# RPi_relay_board.net
KiCad netlist of a schematic drawn in EAGLE
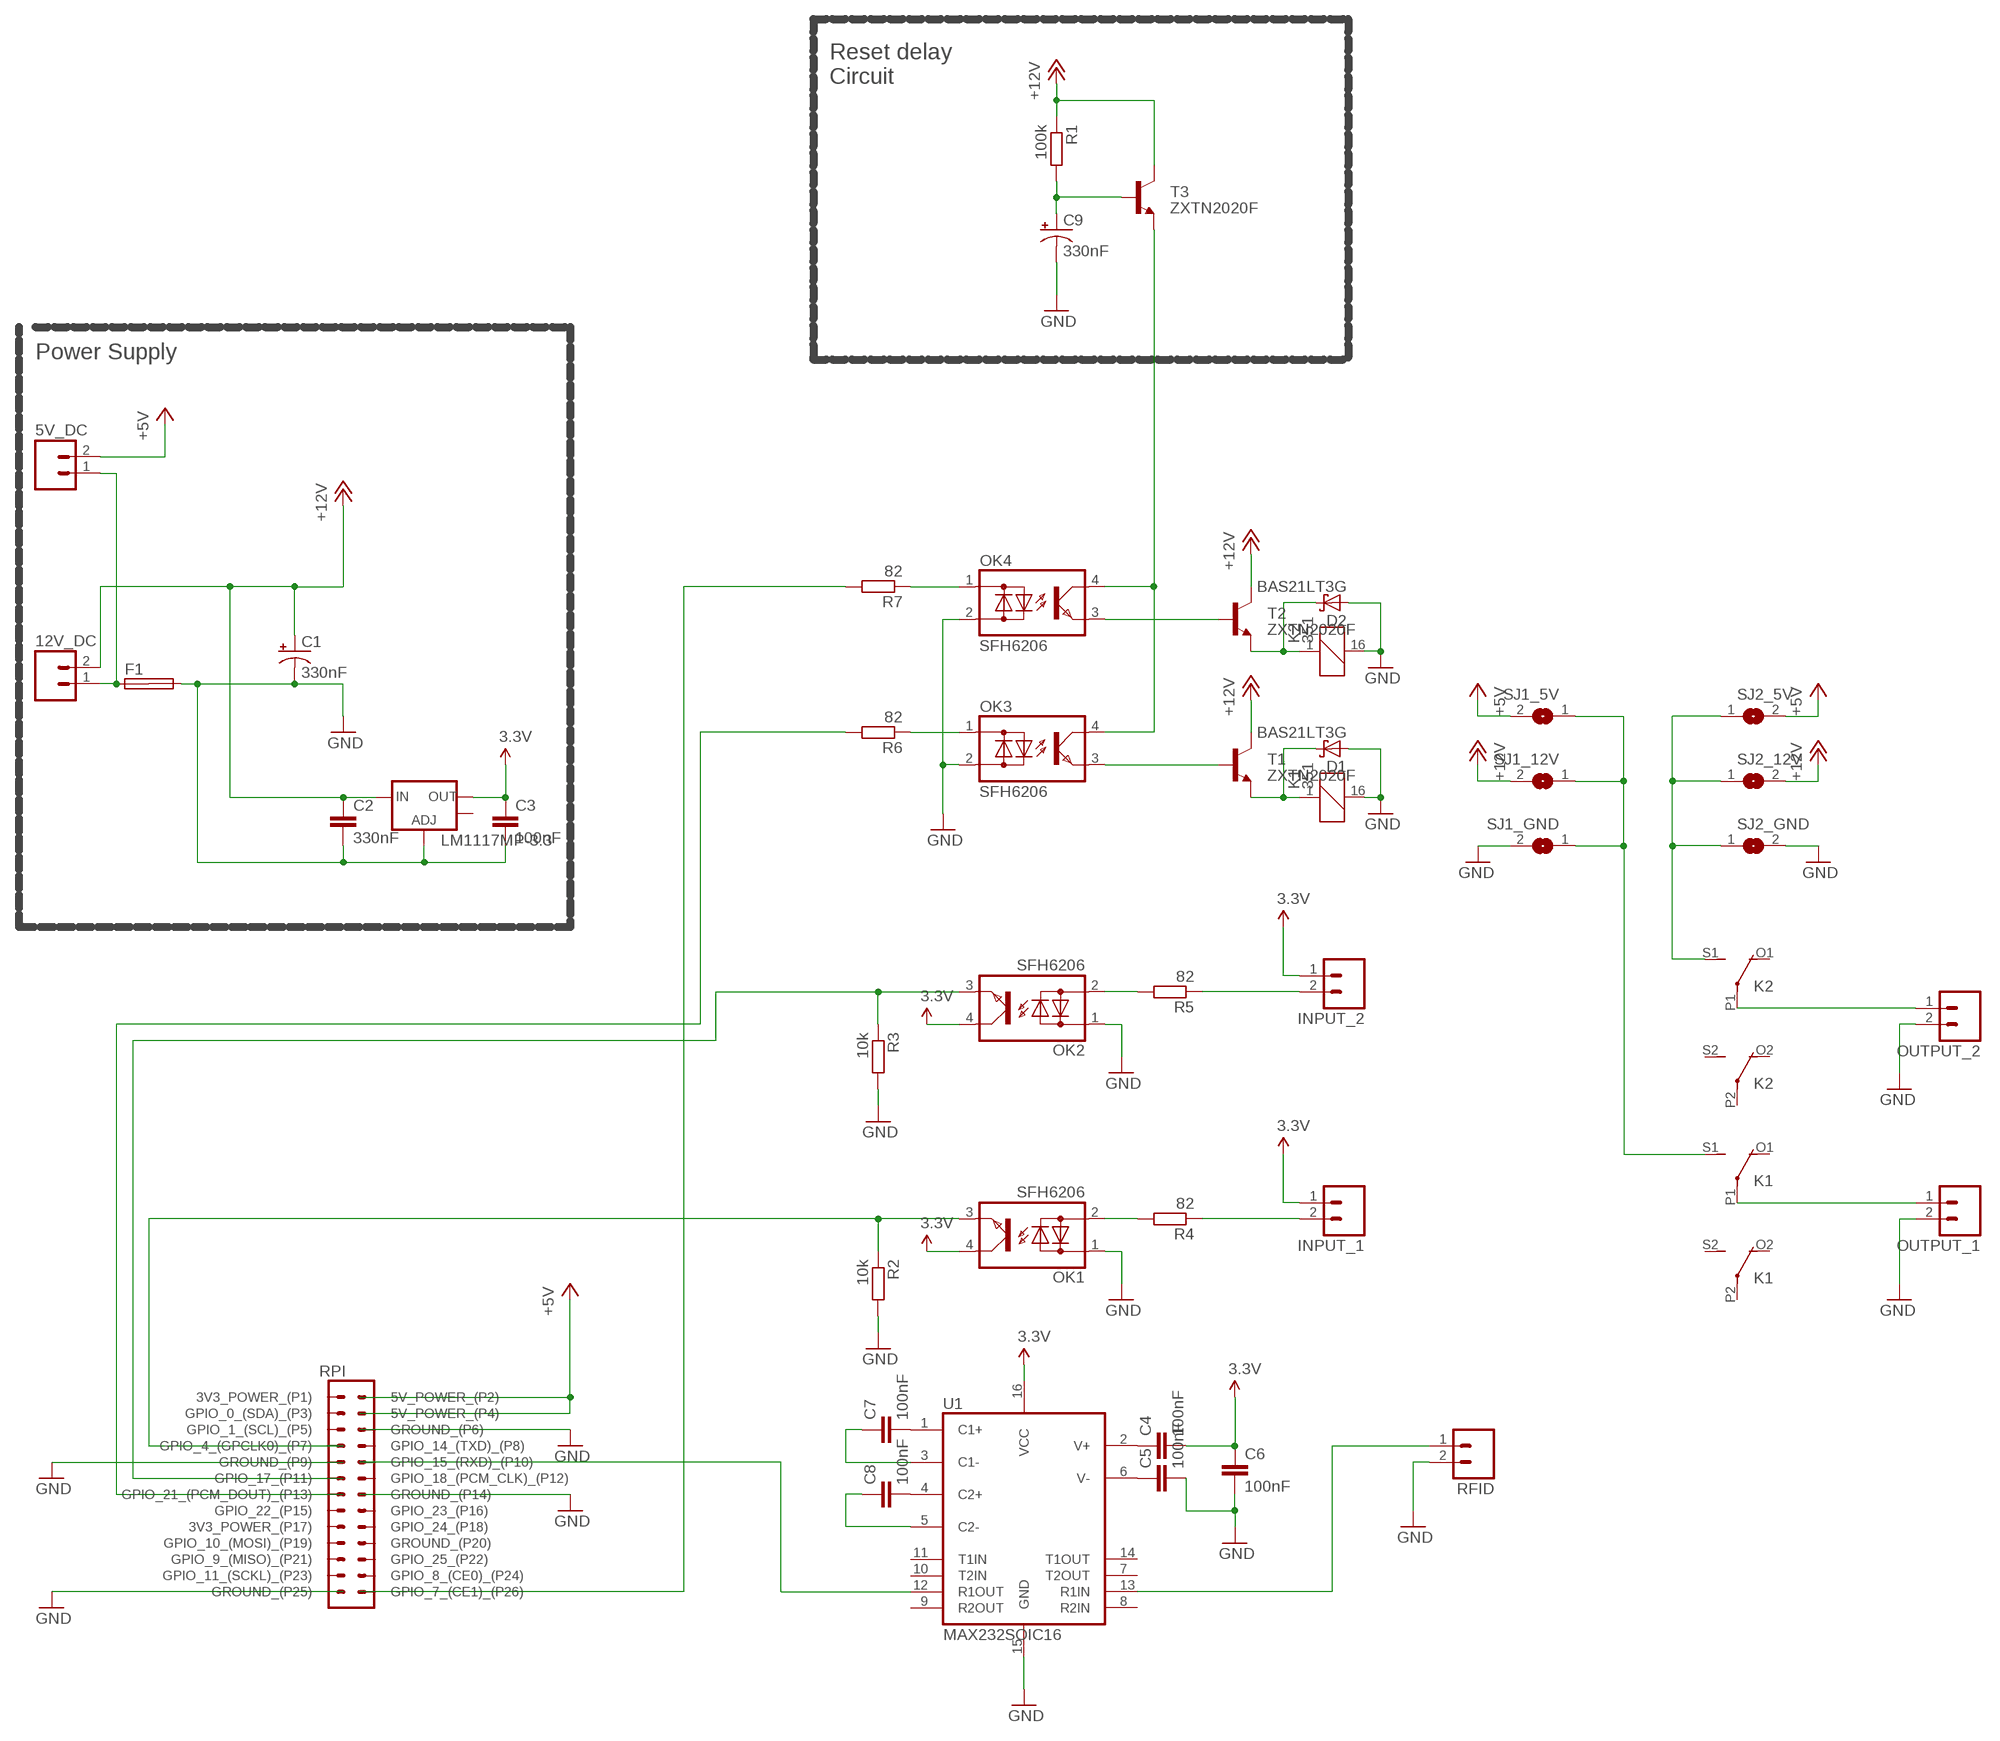
[diagram p0: schematic, sheet 1]

(export (version "E")
  (design (tool "Eeschema 10.0.6"))
  (components
    (comp (ref "5V_DC")
      (value "M02PTH3_5MM")
      (footprint "eagle-import:1X02_LONGPADS")
      (libsource (lib "eagle-import") (part "M02PTH3_5MM"))
    )
    (comp (ref "12V_DC")
      (value "M02PTH3_5MM")
      (footprint "eagle-import:1X02_LONGPADS")
      (libsource (lib "eagle-import") (part "M02PTH3_5MM"))
    )
    (comp (ref "C1")
      (value "330nF")
      (footprint "eagle-import:EIA7343")
      (libsource (lib "eagle-import") (part "CAP_POL7343"))
    )
    (comp (ref "C2")
      (value "330nF")
      (footprint "eagle-import:C3216")
      (libsource (lib "eagle-import") (part "C-EUC3216"))
    )
    (comp (ref "C3")
      (value "100nF")
      (footprint "eagle-import:C3216")
      (libsource (lib "eagle-import") (part "C-EUC3216"))
    )
    (comp (ref "C4")
      (value "100nF")
      (footprint "eagle-import:C2012")
      (libsource (lib "eagle-import") (part "C-EUC2012"))
    )
    (comp (ref "C5")
      (value "100nF")
      (footprint "eagle-import:C2012")
      (libsource (lib "eagle-import") (part "C-EUC2012"))
    )
    (comp (ref "C6")
      (value "100nF")
      (footprint "eagle-import:C2012")
      (libsource (lib "eagle-import") (part "C-EUC2012"))
    )
    (comp (ref "C7")
      (value "100nF")
      (footprint "eagle-import:C2012")
      (libsource (lib "eagle-import") (part "C-EUC2012"))
    )
    (comp (ref "C8")
      (value "100nF")
      (footprint "eagle-import:C2012")
      (libsource (lib "eagle-import") (part "C-EUC2012"))
    )
    (comp (ref "C9")
      (value "330nF")
      (footprint "eagle-import:EIA7343")
      (libsource (lib "eagle-import") (part "CAP_POL7343"))
    )
    (comp (ref "D1")
      (value "BAS21LT3G")
      (footprint "eagle-import:SOT23")
      (libsource (lib "eagle-import") (part "BAS40"))
    )
    (comp (ref "D2")
      (value "BAS21LT3G")
      (footprint "eagle-import:SOT23")
      (libsource (lib "eagle-import") (part "BAS40"))
    )
    (comp (ref "F1")
      (value "SHK20L")
      (footprint "eagle-import:SHK20L")
      (fields (field (name "OC_FARNELL") "unknown") (field (name "OC_NEWARK") "unknown"))
      (libsource (lib "eagle-import") (part "SHK20L"))
    )
    (comp (ref "INPUT_1")
      (value "M02PTH3_5MM")
      (footprint "eagle-import:1X02_LONGPADS")
      (libsource (lib "eagle-import") (part "M02PTH3_5MM"))
    )
    (comp (ref "INPUT_2")
      (value "M02PTH3_5MM")
      (footprint "eagle-import:1X02_LONGPADS")
      (libsource (lib "eagle-import") (part "M02PTH3_5MM"))
    )
    (comp (ref "K1")
      (value "351")
      (footprint "eagle-import:351")
      (libsource (lib "eagle-import") (part "351"))
    )
    (comp (ref "K2")
      (value "351")
      (footprint "eagle-import:351")
      (libsource (lib "eagle-import") (part "351"))
    )
    (comp (ref "LM1117MP-3.3")
      (value "V_REG_LM1117SOT223")
      (footprint "eagle-import:SOT223")
      (libsource (lib "eagle-import") (part "V_REG_LM1117SOT223"))
    )
    (comp (ref "OK1")
      (value "SFH6206")
      (footprint "eagle-import:DIL4-SMD")
      (fields (field (name "MF") "VISHAY/TELEFUNKEN") (field (name "MPN") "SFH6206-3"))
      (libsource (lib "eagle-import") (part "SFH6206"))
    )
    (comp (ref "OK2")
      (value "SFH6206")
      (footprint "eagle-import:DIL4-SMD")
      (fields (field (name "MF") "VISHAY/TELEFUNKEN") (field (name "MPN") "SFH6206-3"))
      (libsource (lib "eagle-import") (part "SFH6206"))
    )
    (comp (ref "OK3")
      (value "SFH6206")
      (footprint "eagle-import:DIL4-SMD")
      (fields (field (name "MF") "VISHAY/TELEFUNKEN") (field (name "MPN") "SFH6206-3"))
      (libsource (lib "eagle-import") (part "SFH6206"))
    )
    (comp (ref "OK4")
      (value "SFH6206")
      (footprint "eagle-import:DIL4-SMD")
      (fields (field (name "MF") "VISHAY/TELEFUNKEN") (field (name "MPN") "SFH6206-3"))
      (libsource (lib "eagle-import") (part "SFH6206"))
    )
    (comp (ref "OUTPUT_1")
      (value "M02PTH3_5MM")
      (footprint "eagle-import:1X02_LONGPADS")
      (libsource (lib "eagle-import") (part "M02PTH3_5MM"))
    )
    (comp (ref "OUTPUT_2")
      (value "M02PTH3_5MM")
      (footprint "eagle-import:1X02_LONGPADS")
      (libsource (lib "eagle-import") (part "M02PTH3_5MM"))
    )
    (comp (ref "R1")
      (value "100k")
      (footprint "eagle-import:M0805")
      (libsource (lib "eagle-import") (part "R-EU_M0805"))
    )
    (comp (ref "R2")
      (value "10k")
      (footprint "eagle-import:M0805")
      (libsource (lib "eagle-import") (part "R-EU_M0805"))
    )
    (comp (ref "R3")
      (value "10k")
      (footprint "eagle-import:M0805")
      (libsource (lib "eagle-import") (part "R-EU_M0805"))
    )
    (comp (ref "R4")
      (value "82")
      (footprint "eagle-import:M0805")
      (libsource (lib "eagle-import") (part "R-EU_M0805"))
    )
    (comp (ref "R5")
      (value "82")
      (footprint "eagle-import:M0805")
      (libsource (lib "eagle-import") (part "R-EU_M0805"))
    )
    (comp (ref "R6")
      (value "82")
      (footprint "eagle-import:M0805")
      (libsource (lib "eagle-import") (part "R-EU_M0805"))
    )
    (comp (ref "R7")
      (value "82")
      (footprint "eagle-import:M0805")
      (libsource (lib "eagle-import") (part "R-EU_M0805"))
    )
    (comp (ref "RFID")
      (value "M02PTH3_5MM")
      (footprint "eagle-import:1X02_LONGPADS")
      (libsource (lib "eagle-import") (part "M02PTH3_5MM"))
    )
    (comp (ref "RPI")
      (value "PINHD-2X13")
      (footprint "eagle-import:2X13")
      (libsource (lib "eagle-import") (part "PINHD-2X13"))
    )
    (comp (ref "SJ1_5V")
      (value "SJW")
      (footprint "eagle-import:SJW")
      (libsource (lib "eagle-import") (part "SJW"))
    )
    (comp (ref "SJ1_12V")
      (value "SJW")
      (footprint "eagle-import:SJW")
      (libsource (lib "eagle-import") (part "SJW"))
    )
    (comp (ref "SJ1_GND")
      (value "SJW")
      (footprint "eagle-import:SJW")
      (libsource (lib "eagle-import") (part "SJW"))
    )
    (comp (ref "SJ2_5V")
      (value "SJW")
      (footprint "eagle-import:SJW")
      (libsource (lib "eagle-import") (part "SJW"))
    )
    (comp (ref "SJ2_12V")
      (value "SJW")
      (footprint "eagle-import:SJW")
      (libsource (lib "eagle-import") (part "SJW"))
    )
    (comp (ref "SJ2_GND")
      (value "SJW")
      (footprint "eagle-import:SJW")
      (libsource (lib "eagle-import") (part "SJW"))
    )
    (comp (ref "T1")
      (value "ZXTN2020F")
      (footprint "eagle-import:SOT23")
      (libsource (lib "eagle-import") (part "TRANSISTOR_NPNSOT23"))
    )
    (comp (ref "T2")
      (value "ZXTN2020F")
      (footprint "eagle-import:SOT23")
      (libsource (lib "eagle-import") (part "TRANSISTOR_NPNSOT23"))
    )
    (comp (ref "T3")
      (value "ZXTN2020F")
      (footprint "eagle-import:SOT23")
      (libsource (lib "eagle-import") (part "TRANSISTOR_NPNSOT23"))
    )
    (comp (ref "U1")
      (value "MAX232SOIC16")
      (footprint "eagle-import:SO016")
      (libsource (lib "eagle-import") (part "MAX232SOIC16"))
    )
  )
  (nets
    (net (code "1") (name "+5V") (class "Default")
      (node (ref "5V_DC") (pin "2") (pinfunction "2_2") (pintype "passive"))
      (node (ref "RPI") (pin "2") (pinfunction "5V_POWER_(P2)_2") (pintype "bidirectional"))
      (node (ref "RPI") (pin "4") (pinfunction "5V_POWER_(P4)_4") (pintype "bidirectional"))
      (node (ref "SJ1_5V") (pin "2") (pinfunction "2_2") (pintype "passive"))
      (node (ref "SJ2_5V") (pin "2") (pinfunction "2_2") (pintype "passive"))
    )
    (net (code "2") (name "+12V") (class "Default")
      (node (ref "12V_DC") (pin "2") (pinfunction "2_2") (pintype "passive"))
      (node (ref "C1") (pin "A") (pinfunction "+_A") (pintype "passive"))
      (node (ref "C2") (pin "1") (pinfunction "1_1") (pintype "passive"))
      (node (ref "LM1117MP-3.3") (pin "3") (pinfunction "IN_3") (pintype "input"))
      (node (ref "R1") (pin "1") (pinfunction "1_1") (pintype "passive"))
      (node (ref "SJ1_12V") (pin "2") (pinfunction "2_2") (pintype "passive"))
      (node (ref "SJ2_12V") (pin "2") (pinfunction "2_2") (pintype "passive"))
      (node (ref "T1") (pin "3") (pinfunction "C_3") (pintype "passive"))
      (node (ref "T2") (pin "3") (pinfunction "C_3") (pintype "passive"))
      (node (ref "T3") (pin "3") (pinfunction "C_3") (pintype "passive"))
    )
    (net (code "3") (name "3.3V") (class "Default")
      (node (ref "C3") (pin "1") (pinfunction "1_1") (pintype "passive"))
      (node (ref "C4") (pin "2") (pinfunction "2_2") (pintype "passive"))
      (node (ref "C6") (pin "1") (pinfunction "1_1") (pintype "passive"))
      (node (ref "INPUT_1") (pin "1") (pinfunction "1_1") (pintype "passive"))
      (node (ref "INPUT_2") (pin "1") (pinfunction "1_1") (pintype "passive"))
      (node (ref "LM1117MP-3.3") (pin "2") (pinfunction "OUT_2") (pintype "output"))
      (node (ref "OK1") (pin "4") (pinfunction "C_4") (pintype "passive"))
      (node (ref "OK2") (pin "4") (pinfunction "C_4") (pintype "passive"))
      (node (ref "U1") (pin "16") (pinfunction "VCC_16") (pintype "bidirectional"))
    )
    (net (code "4") (name "GND") (class "Default")
      (node (ref "C1") (pin "C") (pinfunction "-_C") (pintype "passive"))
      (node (ref "C2") (pin "2") (pinfunction "2_2") (pintype "passive"))
      (node (ref "C3") (pin "2") (pinfunction "2_2") (pintype "passive"))
      (node (ref "C5") (pin "2") (pinfunction "2_2") (pintype "passive"))
      (node (ref "C6") (pin "2") (pinfunction "2_2") (pintype "passive"))
      (node (ref "C9") (pin "C") (pinfunction "-_C") (pintype "passive"))
      (node (ref "D1") (pin "1") (pinfunction "A_1") (pintype "passive"))
      (node (ref "D2") (pin "1") (pinfunction "A_1") (pintype "passive"))
      (node (ref "F1") (pin "2A") (pinfunction "2A_2A") (pintype "passive"))
      (node (ref "K1") (pin "16") (pinfunction "2_16") (pintype "passive"))
      (node (ref "K2") (pin "16") (pinfunction "2_16") (pintype "passive"))
      (node (ref "LM1117MP-3.3") (pin "1") (pinfunction "ADJ_1") (pintype "input"))
      (node (ref "OK1") (pin "1") (pinfunction "AC1_1") (pintype "passive"))
      (node (ref "OK2") (pin "1") (pinfunction "AC1_1") (pintype "passive"))
      (node (ref "OK3") (pin "2") (pinfunction "AC2_2") (pintype "passive"))
      (node (ref "OK4") (pin "2") (pinfunction "AC2_2") (pintype "passive"))
      (node (ref "OUTPUT_1") (pin "2") (pinfunction "2_2") (pintype "passive"))
      (node (ref "OUTPUT_2") (pin "2") (pinfunction "2_2") (pintype "passive"))
      (node (ref "R2") (pin "2") (pinfunction "2_2") (pintype "passive"))
      (node (ref "R3") (pin "2") (pinfunction "2_2") (pintype "passive"))
      (node (ref "RFID") (pin "2") (pinfunction "2_2") (pintype "passive"))
      (node (ref "RPI") (pin "14") (pinfunction "GROUND_(P14)_14") (pintype "bidirectional"))
      (node (ref "RPI") (pin "25") (pinfunction "GROUND_(P25)_25") (pintype "bidirectional"))
      (node (ref "RPI") (pin "6") (pinfunction "GROUND_(P6)_6") (pintype "bidirectional"))
      (node (ref "RPI") (pin "9") (pinfunction "GROUND_(P9)_9") (pintype "bidirectional"))
      (node (ref "SJ1_GND") (pin "2") (pinfunction "2_2") (pintype "passive"))
      (node (ref "SJ2_GND") (pin "2") (pinfunction "2_2") (pintype "passive"))
      (node (ref "U1") (pin "15") (pinfunction "GND_15") (pintype "bidirectional"))
    )
    (net (code "5") (name "Net-(12V_DC-Pad1)") (class "Default")
      (node (ref "12V_DC") (pin "1") (pinfunction "1_1") (pintype "passive"))
      (node (ref "5V_DC") (pin "1") (pinfunction "1_1") (pintype "passive"))
      (node (ref "F1") (pin "1A") (pinfunction "1A_1A") (pintype "passive"))
    )
    (net (code "6") (name "Net-(C9-+)") (class "Default")
      (node (ref "C9") (pin "A") (pinfunction "+_A") (pintype "passive"))
      (node (ref "R1") (pin "2") (pinfunction "2_2") (pintype "passive"))
      (node (ref "T3") (pin "1") (pinfunction "B_1") (pintype "passive"))
    )
    (net (code "7") (name "Net-(D1-C)") (class "Default")
      (node (ref "D1") (pin "3") (pinfunction "C_3") (pintype "passive"))
      (node (ref "K1") (pin "1") (pinfunction "1_1") (pintype "passive"))
      (node (ref "T1") (pin "2") (pinfunction "E_2") (pintype "passive"))
    )
    (net (code "8") (name "Net-(D2-C)") (class "Default")
      (node (ref "D2") (pin "3") (pinfunction "C_3") (pintype "passive"))
      (node (ref "K2") (pin "1") (pinfunction "1_1") (pintype "passive"))
      (node (ref "T2") (pin "2") (pinfunction "E_2") (pintype "passive"))
    )
    (net (code "9") (name "Net-(INPUT_1-Pad2)") (class "Default")
      (node (ref "INPUT_1") (pin "2") (pinfunction "2_2") (pintype "passive"))
      (node (ref "R4") (pin "1") (pinfunction "1_1") (pintype "passive"))
    )
    (net (code "10") (name "Net-(INPUT_2-Pad2)") (class "Default")
      (node (ref "INPUT_2") (pin "2") (pinfunction "2_2") (pintype "passive"))
      (node (ref "R5") (pin "1") (pinfunction "1_1") (pintype "passive"))
    )
    (net (code "11") (name "Net-(K1B-P)") (class "Default")
      (node (ref "K1") (pin "P1") (pinfunction "P_P1") (pintype "passive"))
      (node (ref "OUTPUT_1") (pin "1") (pinfunction "1_1") (pintype "passive"))
    )
    (net (code "12") (name "Net-(K1B-S)") (class "Default")
      (node (ref "K1") (pin "S1") (pinfunction "S_S1") (pintype "passive"))
      (node (ref "SJ1_12V") (pin "1") (pinfunction "1_1") (pintype "passive"))
      (node (ref "SJ1_5V") (pin "1") (pinfunction "1_1") (pintype "passive"))
      (node (ref "SJ1_GND") (pin "1") (pinfunction "1_1") (pintype "passive"))
    )
    (net (code "13") (name "Net-(K2B-P)") (class "Default")
      (node (ref "K2") (pin "P1") (pinfunction "P_P1") (pintype "passive"))
      (node (ref "OUTPUT_2") (pin "1") (pinfunction "1_1") (pintype "passive"))
    )
    (net (code "14") (name "Net-(K2B-S)") (class "Default")
      (node (ref "K2") (pin "S1") (pinfunction "S_S1") (pintype "passive"))
      (node (ref "SJ2_12V") (pin "1") (pinfunction "1_1") (pintype "passive"))
      (node (ref "SJ2_5V") (pin "1") (pinfunction "1_1") (pintype "passive"))
      (node (ref "SJ2_GND") (pin "1") (pinfunction "1_1") (pintype "passive"))
    )
    (net (code "15") (name "Net-(OK1-AC2)") (class "Default")
      (node (ref "OK1") (pin "2") (pinfunction "AC2_2") (pintype "passive"))
      (node (ref "R4") (pin "2") (pinfunction "2_2") (pintype "passive"))
    )
    (net (code "16") (name "Net-(OK1-E)") (class "Default")
      (node (ref "OK1") (pin "3") (pinfunction "E_3") (pintype "passive"))
      (node (ref "R2") (pin "1") (pinfunction "1_1") (pintype "passive"))
      (node (ref "RPI") (pin "7") (pinfunction "GPIO_4_(GPCLK0)_(P7)_7") (pintype "bidirectional"))
    )
    (net (code "17") (name "Net-(OK2-AC2)") (class "Default")
      (node (ref "OK2") (pin "2") (pinfunction "AC2_2") (pintype "passive"))
      (node (ref "R5") (pin "2") (pinfunction "2_2") (pintype "passive"))
    )
    (net (code "18") (name "Net-(OK2-E)") (class "Default")
      (node (ref "OK2") (pin "3") (pinfunction "E_3") (pintype "passive"))
      (node (ref "R3") (pin "1") (pinfunction "1_1") (pintype "passive"))
      (node (ref "RPI") (pin "11") (pinfunction "GPIO_17_(P11)_11") (pintype "bidirectional"))
    )
    (net (code "19") (name "Net-(OK3-AC1)") (class "Default")
      (node (ref "OK3") (pin "1") (pinfunction "AC1_1") (pintype "passive"))
      (node (ref "R6") (pin "1") (pinfunction "1_1") (pintype "passive"))
    )
    (net (code "20") (name "Net-(OK3-C)") (class "Default")
      (node (ref "OK3") (pin "4") (pinfunction "C_4") (pintype "passive"))
      (node (ref "OK4") (pin "4") (pinfunction "C_4") (pintype "passive"))
      (node (ref "T3") (pin "2") (pinfunction "E_2") (pintype "passive"))
    )
    (net (code "21") (name "Net-(OK3-E)") (class "Default")
      (node (ref "OK3") (pin "3") (pinfunction "E_3") (pintype "passive"))
      (node (ref "T1") (pin "1") (pinfunction "B_1") (pintype "passive"))
    )
    (net (code "22") (name "Net-(OK4-AC1)") (class "Default")
      (node (ref "OK4") (pin "1") (pinfunction "AC1_1") (pintype "passive"))
      (node (ref "R7") (pin "1") (pinfunction "1_1") (pintype "passive"))
    )
    (net (code "23") (name "Net-(OK4-E)") (class "Default")
      (node (ref "OK4") (pin "3") (pinfunction "E_3") (pintype "passive"))
      (node (ref "T2") (pin "1") (pinfunction "B_1") (pintype "passive"))
    )
    (net (code "24") (name "Net-(RPI-GPIO_7_(CE1)_(P26))") (class "Default")
      (node (ref "R7") (pin "2") (pinfunction "2_2") (pintype "passive"))
      (node (ref "RPI") (pin "26") (pinfunction "GPIO_7_(CE1)_(P26)_26") (pintype "bidirectional"))
    )
    (net (code "25") (name "Net-(RPI-GPIO_15_(RXD)_(P10))") (class "Default")
      (node (ref "RPI") (pin "10") (pinfunction "GPIO_15_(RXD)_(P10)_10") (pintype "bidirectional"))
      (node (ref "U1") (pin "12") (pinfunction "R1OUT_12") (pintype "output"))
    )
    (net (code "26") (name "Net-(RPI-GPIO_21_(PCM_DOUT)_(P13))") (class "Default")
      (node (ref "R6") (pin "2") (pinfunction "2_2") (pintype "passive"))
      (node (ref "RPI") (pin "13") (pinfunction "GPIO_21_(PCM_DOUT)_(P13)_13") (pintype "bidirectional"))
    )
    (net (code "27") (name "Net-(U1-C1+)") (class "Default")
      (node (ref "C7") (pin "2") (pinfunction "2_2") (pintype "passive"))
      (node (ref "U1") (pin "1") (pinfunction "C1+_1") (pintype "bidirectional"))
    )
    (net (code "28") (name "Net-(U1-C1-)") (class "Default")
      (node (ref "C7") (pin "1") (pinfunction "1_1") (pintype "passive"))
      (node (ref "U1") (pin "3") (pinfunction "C1-_3") (pintype "bidirectional"))
    )
    (net (code "29") (name "Net-(U1-C2+)") (class "Default")
      (node (ref "C8") (pin "2") (pinfunction "2_2") (pintype "passive"))
      (node (ref "U1") (pin "4") (pinfunction "C2+_4") (pintype "bidirectional"))
    )
    (net (code "30") (name "Net-(U1-C2-)") (class "Default")
      (node (ref "C8") (pin "1") (pinfunction "1_1") (pintype "passive"))
      (node (ref "U1") (pin "5") (pinfunction "C2-_5") (pintype "bidirectional"))
    )
    (net (code "31") (name "Net-(U1-R1IN)") (class "Default")
      (node (ref "RFID") (pin "1") (pinfunction "1_1") (pintype "passive"))
      (node (ref "U1") (pin "13") (pinfunction "R1IN_13") (pintype "input"))
    )
    (net (code "32") (name "Net-(U1-V+)") (class "Default")
      (node (ref "C4") (pin "1") (pinfunction "1_1") (pintype "passive"))
      (node (ref "U1") (pin "2") (pinfunction "V+_2") (pintype "bidirectional"))
    )
    (net (code "33") (name "Net-(U1-V-)") (class "Default")
      (node (ref "C5") (pin "1") (pinfunction "1_1") (pintype "passive"))
      (node (ref "U1") (pin "6") (pinfunction "V-_6") (pintype "bidirectional"))
    )
    (net (code "34") (name "unconnected-(F1-Pad1B)") (class "Default")
      (node (ref "F1") (pin "1B") (pinfunction "1B_1B") (pintype "passive"))
    )
    (net (code "35") (name "unconnected-(F1-Pad2B)") (class "Default")
      (node (ref "F1") (pin "2B") (pinfunction "2B_2B") (pintype "passive"))
    )
    (net (code "36") (name "unconnected-(K1B-O-PadO1)") (class "Default")
      (node (ref "K1") (pin "O1") (pinfunction "O_O1") (pintype "passive"))
    )
    (net (code "37") (name "unconnected-(K1C-O-PadO2)") (class "Default")
      (node (ref "K1") (pin "O2") (pinfunction "O_O2") (pintype "passive"))
    )
    (net (code "38") (name "unconnected-(K1C-P-PadP2)") (class "Default")
      (node (ref "K1") (pin "P2") (pinfunction "P_P2") (pintype "passive"))
    )
    (net (code "39") (name "unconnected-(K1C-S-PadS2)") (class "Default")
      (node (ref "K1") (pin "S2") (pinfunction "S_S2") (pintype "passive"))
    )
    (net (code "40") (name "unconnected-(K2B-O-PadO1)") (class "Default")
      (node (ref "K2") (pin "O1") (pinfunction "O_O1") (pintype "passive"))
    )
    (net (code "41") (name "unconnected-(K2C-O-PadO2)") (class "Default")
      (node (ref "K2") (pin "O2") (pinfunction "O_O2") (pintype "passive"))
    )
    (net (code "42") (name "unconnected-(K2C-P-PadP2)") (class "Default")
      (node (ref "K2") (pin "P2") (pinfunction "P_P2") (pintype "passive"))
    )
    (net (code "43") (name "unconnected-(K2C-S-PadS2)") (class "Default")
      (node (ref "K2") (pin "S2") (pinfunction "S_S2") (pintype "passive"))
    )
    (net (code "44") (name "unconnected-(LM1117MP-3.3-OUT-Pad4)") (class "Default")
      (node (ref "LM1117MP-3.3") (pin "4") (pinfunction "OUT_4") (pintype "output"))
    )
    (net (code "45") (name "unconnected-(RPI-3V3_POWER_(P1)-Pad1)") (class "Default")
      (node (ref "RPI") (pin "1") (pinfunction "3V3_POWER_(P1)_1") (pintype "bidirectional"))
    )
    (net (code "46") (name "unconnected-(RPI-3V3_POWER_(P17)-Pad17)") (class "Default")
      (node (ref "RPI") (pin "17") (pinfunction "3V3_POWER_(P17)_17") (pintype "bidirectional"))
    )
    (net (code "47") (name "unconnected-(RPI-GPIO_0_(SDA)_(P3)-Pad3)") (class "Default")
      (node (ref "RPI") (pin "3") (pinfunction "GPIO_0_(SDA)_(P3)_3") (pintype "bidirectional"))
    )
    (net (code "48") (name "unconnected-(RPI-GPIO_1_(SCL)_(P5)-Pad5)") (class "Default")
      (node (ref "RPI") (pin "5") (pinfunction "GPIO_1_(SCL)_(P5)_5") (pintype "bidirectional"))
    )
    (net (code "49") (name "unconnected-(RPI-GPIO_8_(CE0)_(P24)-Pad24)") (class "Default")
      (node (ref "RPI") (pin "24") (pinfunction "GPIO_8_(CE0)_(P24)_24") (pintype "bidirectional"))
    )
    (net (code "50") (name "unconnected-(RPI-GPIO_9_(MISO)_(P21)-Pad21)") (class "Default")
      (node (ref "RPI") (pin "21") (pinfunction "GPIO_9_(MISO)_(P21)_21") (pintype "bidirectional"))
    )
    (net (code "51") (name "unconnected-(RPI-GPIO_10_(MOSI)_(P19)-Pad19)") (class "Default")
      (node (ref "RPI") (pin "19") (pinfunction "GPIO_10_(MOSI)_(P19)_19") (pintype "bidirectional"))
    )
    (net (code "52") (name "unconnected-(RPI-GPIO_11_(SCKL)_(P23)-Pad23)") (class "Default")
      (node (ref "RPI") (pin "23") (pinfunction "GPIO_11_(SCKL)_(P23)_23") (pintype "bidirectional"))
    )
    (net (code "53") (name "unconnected-(RPI-GPIO_14_(TXD)_(P8)-Pad8)") (class "Default")
      (node (ref "RPI") (pin "8") (pinfunction "GPIO_14_(TXD)_(P8)_8") (pintype "bidirectional"))
    )
    (net (code "54") (name "unconnected-(RPI-GPIO_18_(PCM_CLK)_(P12)-Pad12)") (class "Default")
      (node (ref "RPI") (pin "12") (pinfunction "GPIO_18_(PCM_CLK)_(P12)_12") (pintype "bidirectional"))
    )
    (net (code "55") (name "unconnected-(RPI-GPIO_22_(P15)-Pad15)") (class "Default")
      (node (ref "RPI") (pin "15") (pinfunction "GPIO_22_(P15)_15") (pintype "bidirectional"))
    )
    (net (code "56") (name "unconnected-(RPI-GPIO_23_(P16)-Pad16)") (class "Default")
      (node (ref "RPI") (pin "16") (pinfunction "GPIO_23_(P16)_16") (pintype "bidirectional"))
    )
    (net (code "57") (name "unconnected-(RPI-GPIO_24_(P18)-Pad18)") (class "Default")
      (node (ref "RPI") (pin "18") (pinfunction "GPIO_24_(P18)_18") (pintype "bidirectional"))
    )
    (net (code "58") (name "unconnected-(RPI-GPIO_25_(P22)-Pad22)") (class "Default")
      (node (ref "RPI") (pin "22") (pinfunction "GPIO_25_(P22)_22") (pintype "bidirectional"))
    )
    (net (code "59") (name "unconnected-(RPI-GROUND_(P20)-Pad20)") (class "Default")
      (node (ref "RPI") (pin "20") (pinfunction "GROUND_(P20)_20") (pintype "bidirectional"))
    )
    (net (code "60") (name "unconnected-(U1-R2IN-Pad8)") (class "Default")
      (node (ref "U1") (pin "8") (pinfunction "R2IN_8") (pintype "input"))
    )
    (net (code "61") (name "unconnected-(U1-R2OUT-Pad9)") (class "Default")
      (node (ref "U1") (pin "9") (pinfunction "R2OUT_9") (pintype "output"))
    )
    (net (code "62") (name "unconnected-(U1-T1IN-Pad11)") (class "Default")
      (node (ref "U1") (pin "11") (pinfunction "T1IN_11") (pintype "input"))
    )
    (net (code "63") (name "unconnected-(U1-T1OUT-Pad14)") (class "Default")
      (node (ref "U1") (pin "14") (pinfunction "T1OUT_14") (pintype "output"))
    )
    (net (code "64") (name "unconnected-(U1-T2IN-Pad10)") (class "Default")
      (node (ref "U1") (pin "10") (pinfunction "T2IN_10") (pintype "input"))
    )
    (net (code "65") (name "unconnected-(U1-T2OUT-Pad7)") (class "Default")
      (node (ref "U1") (pin "7") (pinfunction "T2OUT_7") (pintype "output"))
    )
  )
)
